# LSM6DSOTR.net
KiCad netlist of a schematic drawn in Altium Designer
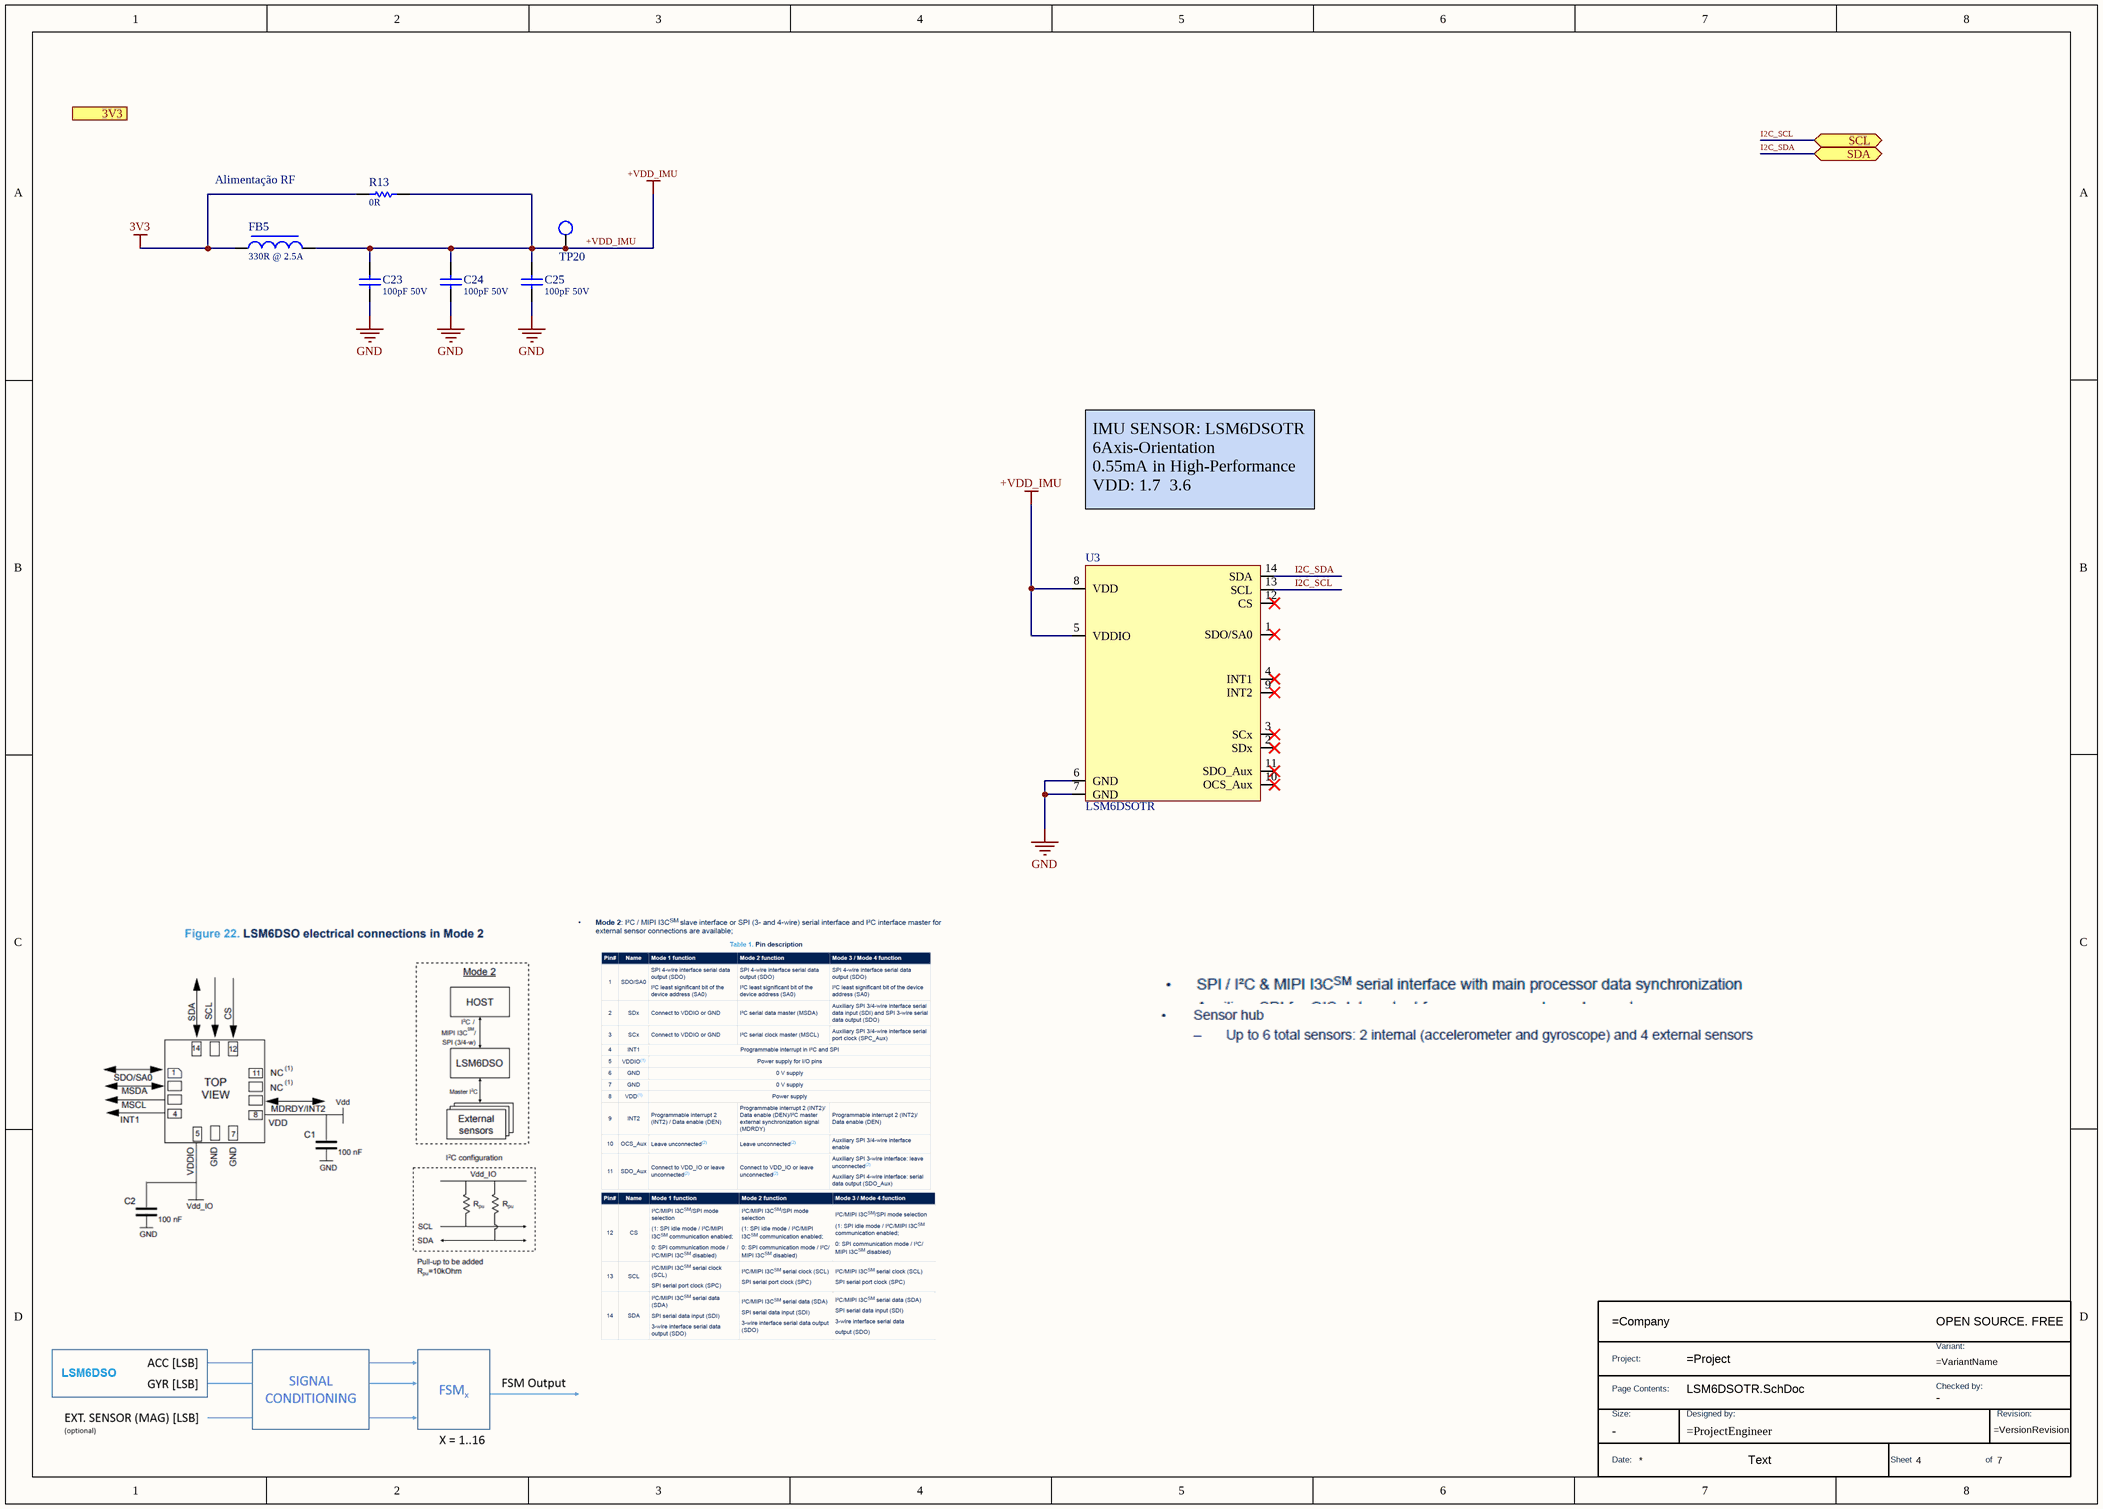
[diagram p0: LSM6DSOTR.SchDoc]

(export (version "E")
  (design (tool "Eeschema 10.0.6"))
  (components
    (comp (ref "*")
      (value "TitleBlock")
      (description "Standard Title Block")
      (fields (field (name "SIZE") "-") (field (name "CHECKED BY") "-"))
      (libsource (lib "OBDH_Ed01r1") (part "TitleBlock"))
    )
    (comp (ref "C23")
      (value "CC0805JRNPO9BN101")
      (footprint "CAP_0805")
      (description "CAP CER 100PF 50V C0G/NPO 0805")
      (fields (field (name "MANUFACTURER") "YAGEO") (field (name "VALOR") "100pF 50V"))
      (libsource (lib "OBDH_Ed02") (part "CC0805JRNPO9BN101"))
    )
    (comp (ref "C24")
      (value "CC0805JRNPO9BN101")
      (footprint "CAP_0805")
      (description "CAP CER 100PF 50V C0G/NPO 0805")
      (fields (field (name "MANUFACTURER") "YAGEO") (field (name "VALOR") "100pF 50V"))
      (libsource (lib "OBDH_Ed02") (part "CC0805JRNPO9BN101"))
    )
    (comp (ref "C25")
      (value "CC0805JRNPO9BN101")
      (footprint "CAP_0805")
      (description "CAP CER 100PF 50V C0G/NPO 0805")
      (fields (field (name "MANUFACTURER") "YAGEO") (field (name "VALOR") "100pF 50V"))
      (libsource (lib "OBDH_Ed02") (part "CC0805JRNPO9BN101"))
    )
    (comp (ref "FB5")
      (value "MPZ2012S331AT000")
      (footprint "IND_0805")
      (description "FERRITE BEAD 330 OHM 0805 1LN")
      (fields (field (name "MANUFACTURER") "TDK Corporation") (field (name "VALOR") "330R @ 2.5A"))
      (libsource (lib "OBDH_Ed02") (part "MPZ2012S331AT000"))
    )
    (comp (ref "R13")
      (value "RC0805JR-070RL")
      (footprint "RES_0805")
      (description "RES 0 OHM JUMPER 1/8W 0805")
      (fields (field (name "MANUFACTURER") "YAGEO") (field (name "VALOR") "0R"))
      (libsource (lib "OBDH_Ed02") (part "RC0805JR-070RL"))
    )
    (comp (ref "TP20")
      (value "TEST_POINT_1.5MM")
      (footprint "TESTPOINT_1.5MM")
      (description "TEST_POINT")
      (libsource (lib "OBDH_Ed02") (part "TEST_POINT_1.5MM"))
    )
    (comp (ref "U3")
      (value "LSM6DSOTR")
      (footprint "IC_IIM-42351")
      (description "Accelerometer, Gyroscope, 6 Axis Sensor I²C, SPI Output")
      (libsource (lib "OBDH_Ed02") (part "LSM6DSOTR"))
    )
  )
  (nets
    (net (code "1") (name "+VDD_IMU") (class "Default")
      (node (ref "C23") (pin "2") (pinfunction "2_2") (pintype "passive"))
      (node (ref "C24") (pin "2") (pinfunction "2_2") (pintype "passive"))
      (node (ref "C25") (pin "2") (pinfunction "2_2") (pintype "passive"))
      (node (ref "FB5") (pin "2") (pinfunction "2_2") (pintype "passive"))
      (node (ref "R13") (pin "2") (pinfunction "2_2") (pintype "passive"))
      (node (ref "TP20") (pin "1") (pinfunction "1_1") (pintype "passive"))
      (node (ref "U3") (pin "5") (pinfunction "VDDIO_5") (pintype "power_in"))
      (node (ref "U3") (pin "8") (pinfunction "VDD_8") (pintype "power_in"))
    )
    (net (code "2") (name "/I2C_SCL") (class "Default")
      (node (ref "U3") (pin "13") (pinfunction "SCL_13") (pintype "bidirectional"))
    )
    (net (code "3") (name "/I2C_SDA") (class "Default")
      (node (ref "U3") (pin "14") (pinfunction "SDA_14") (pintype "bidirectional"))
    )
    (net (code "4") (name "3V3") (class "Default")
      (node (ref "FB5") (pin "1") (pinfunction "1_1") (pintype "passive"))
      (node (ref "R13") (pin "1") (pinfunction "1_1") (pintype "passive"))
    )
    (net (code "5") (name "GND") (class "Default")
      (node (ref "C23") (pin "1") (pinfunction "1_1") (pintype "passive"))
      (node (ref "C24") (pin "1") (pinfunction "1_1") (pintype "passive"))
      (node (ref "C25") (pin "1") (pinfunction "1_1") (pintype "passive"))
      (node (ref "U3") (pin "6") (pinfunction "GND_6") (pintype "power_in"))
      (node (ref "U3") (pin "7") (pinfunction "GND_7") (pintype "power_in"))
    )
    (net (code "6") (name "unconnected-(U3-CS-Pad12)") (class "Default")
      (node (ref "U3") (pin "12") (pinfunction "CS_12") (pintype "bidirectional+no_connect"))
    )
    (net (code "7") (name "unconnected-(U3-INT1-Pad4)") (class "Default")
      (node (ref "U3") (pin "4") (pinfunction "INT1_4") (pintype "bidirectional+no_connect"))
    )
    (net (code "8") (name "unconnected-(U3-INT2-Pad9)") (class "Default")
      (node (ref "U3") (pin "9") (pinfunction "INT2_9") (pintype "bidirectional+no_connect"))
    )
    (net (code "9") (name "unconnected-(U3-OCS_Aux-Pad10)") (class "Default")
      (node (ref "U3") (pin "10") (pinfunction "OCS_Aux_10") (pintype "bidirectional+no_connect"))
    )
    (net (code "10") (name "unconnected-(U3-SCx-Pad3)") (class "Default")
      (node (ref "U3") (pin "3") (pinfunction "SCx_3") (pintype "bidirectional+no_connect"))
    )
    (net (code "11") (name "unconnected-(U3-SDO_Aux-Pad11)") (class "Default")
      (node (ref "U3") (pin "11") (pinfunction "SDO_Aux_11") (pintype "bidirectional+no_connect"))
    )
    (net (code "12") (name "unconnected-(U3-SDO{slash}SA0-Pad1)") (class "Default")
      (node (ref "U3") (pin "1") (pinfunction "SDO/SA0_1") (pintype "bidirectional+no_connect"))
    )
    (net (code "13") (name "unconnected-(U3-SDx-Pad2)") (class "Default")
      (node (ref "U3") (pin "2") (pinfunction "SDx_2") (pintype "bidirectional+no_connect"))
    )
  )
)
